# CAN-Adapter_3_2korr_0622.net
KiCad netlist of a schematic drawn in EAGLE
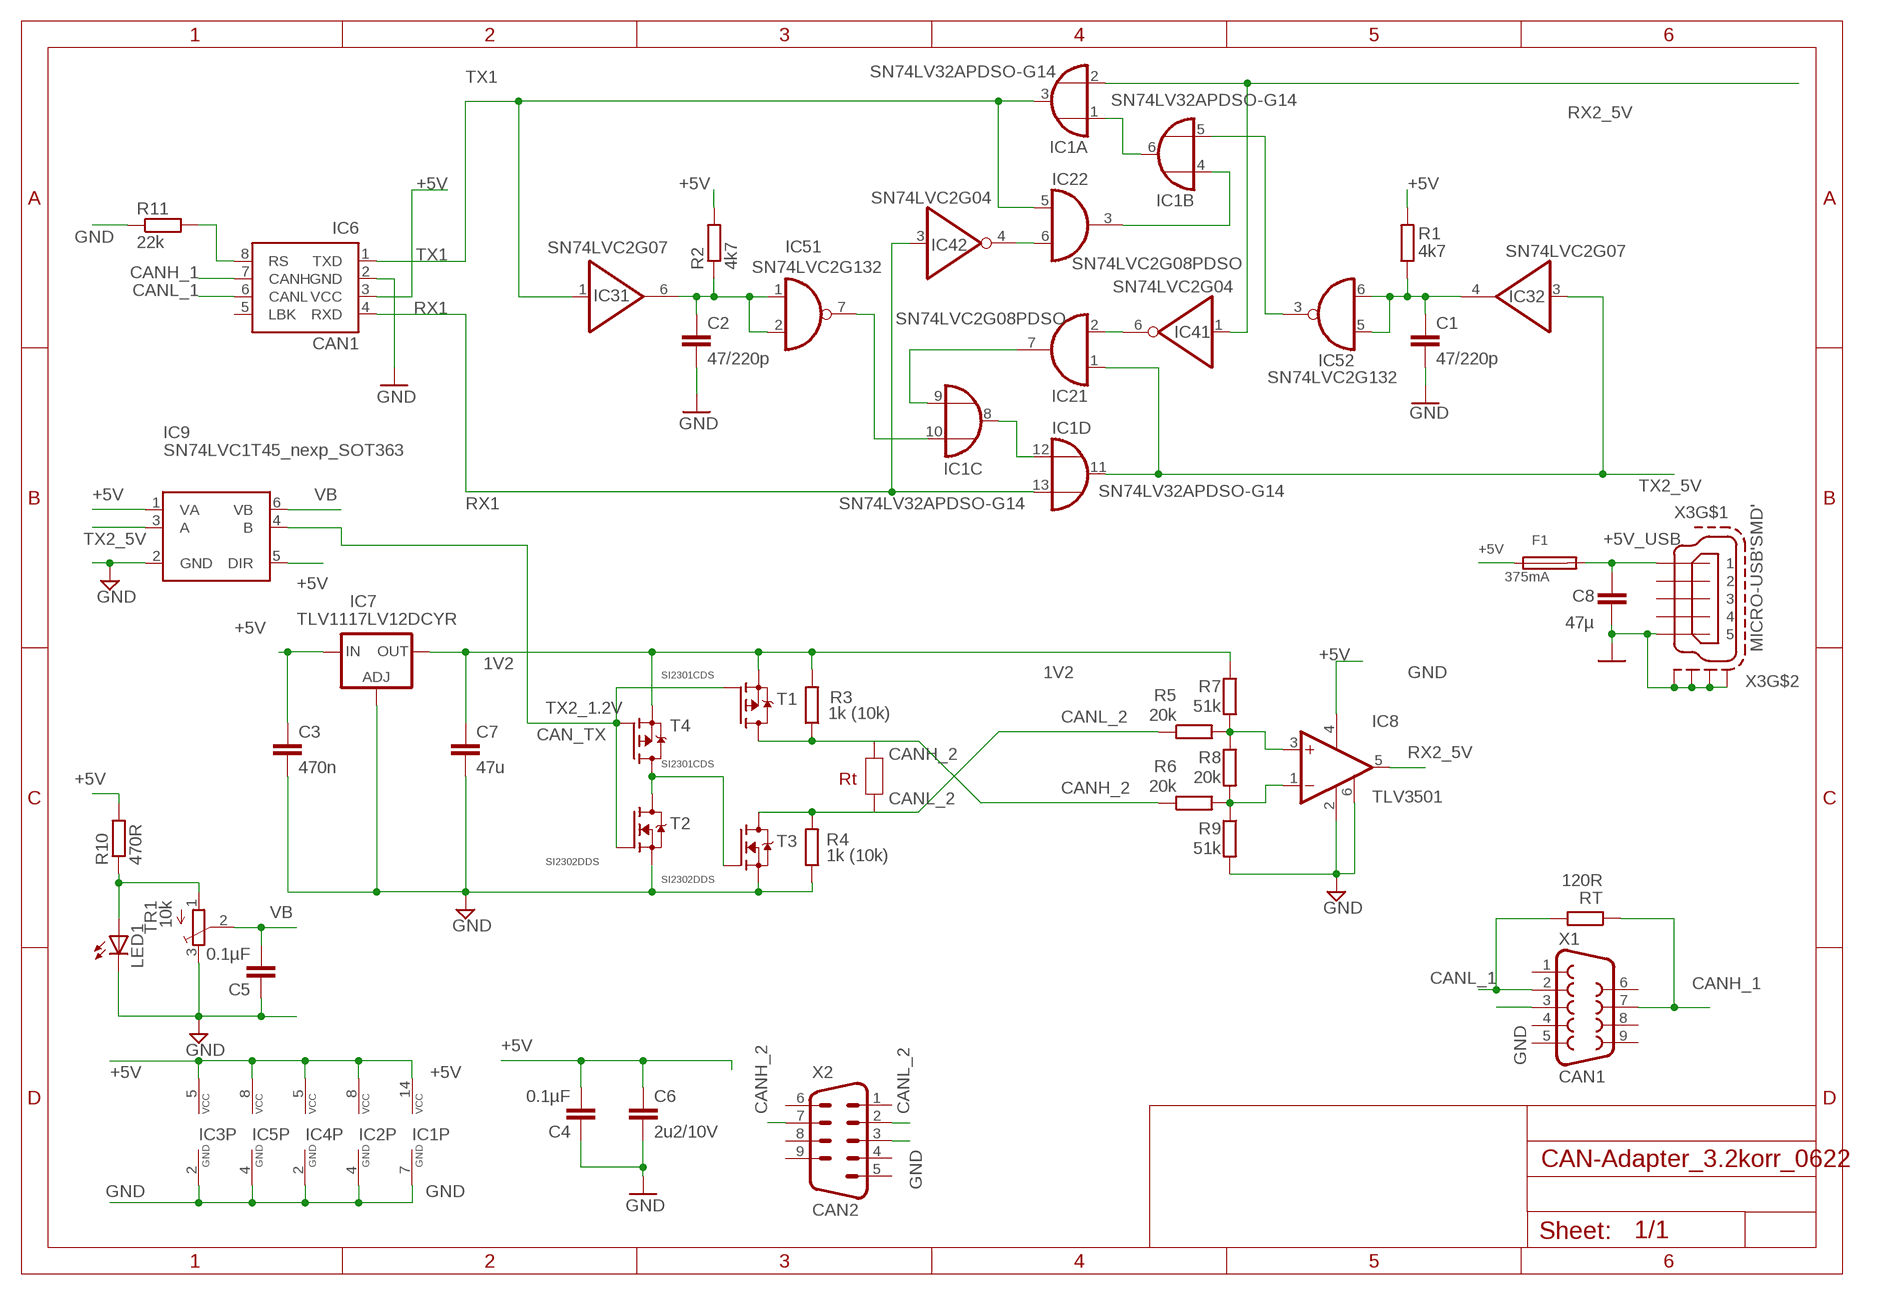
[diagram p0: schematic, sheet 1]

(export (version "E")
  (design (tool "Eeschema 10.0.6"))
  (components
    (comp (ref "C1")
      (value "47/220p")
      (footprint "eagle-import:C0603")
      (libsource (lib "eagle-import") (part "C-EUC0603"))
    )
    (comp (ref "C2")
      (value "47/220p")
      (footprint "eagle-import:C0603")
      (libsource (lib "eagle-import") (part "C-EUC0603"))
    )
    (comp (ref "C3")
      (value "470n")
      (footprint "eagle-import:C1206S")
      (libsource (lib "eagle-import") (part "C-EUC1206S"))
    )
    (comp (ref "C4")
      (value "0.1µF")
      (footprint "eagle-import:C0805")
      (libsource (lib "eagle-import") (part "C-EUC0805"))
    )
    (comp (ref "C5")
      (value "0.1µF")
      (footprint "eagle-import:C0805")
      (libsource (lib "eagle-import") (part "C-EUC0805"))
    )
    (comp (ref "C6")
      (value "2u2/10V")
      (footprint "eagle-import:C0805")
      (libsource (lib "eagle-import") (part "C-EUC0805"))
    )
    (comp (ref "C7")
      (value "47u")
      (footprint "eagle-import:C1206K")
      (libsource (lib "eagle-import") (part "C-EUC1206K"))
    )
    (comp (ref "C8")
      (value "47µ")
      (footprint "eagle-import:C1206K")
      (libsource (lib "eagle-import") (part "C-EUC1206K"))
    )
    (comp (ref "F1")
      (value "375mA")
      (footprint "eagle-import:1206")
      (libsource (lib "eagle-import") (part "SMD-FUSE1206"))
    )
    (comp (ref "IC1")
      (value "SN74LV32APDSO-G14")
      (footprint "eagle-import:PW_R-PDSO-G14")
      (libsource (lib "eagle-import") (part "SN74LV32APDSO-G14"))
    )
    (comp (ref "IC2")
      (value "SN74LVC2G08PDSO")
      (footprint "eagle-import:R-PDSO-G08_DCT")
      (libsource (lib "eagle-import") (part "SN74LVC2G08PDSO"))
    )
    (comp (ref "IC3")
      (value "SN74LVC2G07")
      (footprint "eagle-import:R-PDSO-G06")
      (libsource (lib "eagle-import") (part "SN74LVC2G07DCK"))
    )
    (comp (ref "IC4")
      (value "SN74LVC2G04")
      (footprint "eagle-import:R-PDSO-G06")
      (libsource (lib "eagle-import") (part "SN74LVC2G04DCK"))
    )
    (comp (ref "IC5")
      (value "SN74LVC2G132")
      (footprint "eagle-import:S-PDSO-G08_DCU")
      (libsource (lib "eagle-import") (part "SN74LVC2G132DCU"))
    )
    (comp (ref "IC6")
      (value "CAN1")
      (footprint "eagle-import:SO-08")
      (libsource (lib "eagle-import") (part "SN65233SO-08''"))
    )
    (comp (ref "IC7")
      (value "TLV1117LV12DCYR")
      (footprint "eagle-import:SOT223")
      (libsource (lib "eagle-import") (part "LD117A?S12TR"))
    )
    (comp (ref "IC8")
      (value "TLV3501")
      (footprint "eagle-import:SOT23-6")
      (libsource (lib "eagle-import") (part "TLV3501"))
    )
    (comp (ref "IC9")
      (value "SN74LVC1T45_nexp_SOT363")
      (footprint "eagle-import:SOT363")
      (libsource (lib "eagle-import") (part "SN74AVCH1T45SOT363"))
    )
    (comp (ref "LED1")
      (value "LED3MM")
      (footprint "eagle-import:LED3MM")
      (libsource (lib "eagle-import") (part "LED3MM"))
    )
    (comp (ref "R1")
      (value "4k7")
      (footprint "eagle-import:R0603")
      (libsource (lib "eagle-import") (part "R-EU_R0603"))
    )
    (comp (ref "R2")
      (value "4k7")
      (footprint "eagle-import:R0603")
      (libsource (lib "eagle-import") (part "R-EU_R0603"))
    )
    (comp (ref "R3")
      (value "1k (10k)")
      (footprint "eagle-import:R0603")
      (libsource (lib "eagle-import") (part "R-EU_R0603"))
    )
    (comp (ref "R4")
      (value "1k (10k)")
      (footprint "eagle-import:R0603")
      (libsource (lib "eagle-import") (part "R-EU_R0603"))
    )
    (comp (ref "R5")
      (value "20k")
      (footprint "eagle-import:R0603")
      (libsource (lib "eagle-import") (part "R-EU_R0603"))
    )
    (comp (ref "R6")
      (value "20k")
      (footprint "eagle-import:R0603")
      (libsource (lib "eagle-import") (part "R-EU_R0603"))
    )
    (comp (ref "R7")
      (value "51k")
      (footprint "eagle-import:R0603")
      (libsource (lib "eagle-import") (part "R-EU_R0603"))
    )
    (comp (ref "R8")
      (value "20k")
      (footprint "eagle-import:R0603")
      (libsource (lib "eagle-import") (part "R-EU_R0603"))
    )
    (comp (ref "R9")
      (value "51k")
      (footprint "eagle-import:R0603")
      (libsource (lib "eagle-import") (part "R-EU_R0603"))
    )
    (comp (ref "R10")
      (value "470R")
      (footprint "eagle-import:R0603")
      (libsource (lib "eagle-import") (part "R-EU_R0603"))
    )
    (comp (ref "R11")
      (value "22k")
      (footprint "eagle-import:R0603")
      (libsource (lib "eagle-import") (part "R-EU_R0603"))
    )
    (comp (ref "RT")
      (value "120R")
      (footprint "eagle-import:R0603")
      (libsource (lib "eagle-import") (part "R-EU_R0603"))
    )
    (comp (ref "T1")
      (value "SI2301CDS")
      (footprint "eagle-import:SOT23")
      (libsource (lib "eagle-import") (part "SI2301CDS_PMOS"))
    )
    (comp (ref "T2")
      (value "SI2302DDS")
      (footprint "eagle-import:SOT23")
      (libsource (lib "eagle-import") (part "SI2302DDS_NMOS"))
    )
    (comp (ref "T3")
      (value "SI2302DDS")
      (footprint "eagle-import:SOT23")
      (libsource (lib "eagle-import") (part "SI2302DDS_NMOS"))
    )
    (comp (ref "T4")
      (value "SI2301CDS")
      (footprint "eagle-import:SOT23")
      (libsource (lib "eagle-import") (part "SI2301CDS_PMOS"))
    )
    (comp (ref "TR1")
      (value "10k")
      (footprint "eagle-import:TC33X-2")
      (libsource (lib "eagle-import") (part "TRIM_EU-TC33X-2"))
    )
    (comp (ref "X1")
      (value "CAN1")
      (footprint "eagle-import:F09D")
      (libsource (lib "eagle-import") (part "F09D"))
    )
    (comp (ref "X2")
      (value "CAN2")
      (footprint "eagle-import:M09D")
      (libsource (lib "eagle-import") (part "M09D"))
    )
    (comp (ref "X3")
      (value "MICRO-USB'SMD'")
      (footprint "eagle-import:MICRO-USB_SMD")
      (libsource (lib "eagle-import") (part "MICRO-USB'SMD'"))
    )
  )
  (nets
    (net (code "1") (name "/+5V") (class "Default")
      (node (ref "C3") (pin "1") (pinfunction "1_1") (pintype "passive"))
      (node (ref "C4") (pin "2") (pinfunction "2_2") (pintype "passive"))
      (node (ref "C6") (pin "1") (pinfunction "1_1") (pintype "passive"))
      (node (ref "F1") (pin "P$1") (pinfunction "1_P$1") (pintype "passive"))
      (node (ref "IC1") (pin "14") (pinfunction "VCC_14") (pintype "power_in"))
      (node (ref "IC2") (pin "8") (pinfunction "VCC_8") (pintype "power_in"))
      (node (ref "IC3") (pin "5") (pinfunction "VCC_5") (pintype "power_in"))
      (node (ref "IC4") (pin "5") (pinfunction "VCC_5") (pintype "power_in"))
      (node (ref "IC5") (pin "8") (pinfunction "VCC_8") (pintype "power_in"))
      (node (ref "IC6") (pin "3") (pinfunction "VCC_3") (pintype "input"))
      (node (ref "IC7") (pin "3") (pinfunction "IN_3") (pintype "input"))
      (node (ref "IC8") (pin "4") (pinfunction "V+_4") (pintype "power_in"))
      (node (ref "IC9") (pin "1") (pinfunction "VA_1") (pintype "power_in"))
      (node (ref "IC9") (pin "5") (pinfunction "DIR_5") (pintype "bidirectional"))
      (node (ref "R1") (pin "2") (pinfunction "2_2") (pintype "passive"))
      (node (ref "R10") (pin "2") (pinfunction "2_2") (pintype "passive"))
      (node (ref "R2") (pin "2") (pinfunction "2_2") (pintype "passive"))
    )
    (net (code "2") (name "/+5V_USB") (class "Default")
      (node (ref "C8") (pin "1") (pinfunction "1_1") (pintype "passive"))
      (node (ref "F1") (pin "P$2") (pinfunction "2_P$2") (pintype "passive"))
      (node (ref "X3") (pin "P$1") (pinfunction "1_P$1") (pintype "passive"))
    )
    (net (code "3") (name "/1V2") (class "Default")
      (node (ref "C7") (pin "1") (pinfunction "1_1") (pintype "passive"))
      (node (ref "IC7") (pin "4") (pinfunction "OUT_4") (pintype "passive"))
      (node (ref "R3") (pin "2") (pinfunction "2_2") (pintype "passive"))
      (node (ref "R7") (pin "1") (pinfunction "1_1") (pintype "passive"))
      (node (ref "T1") (pin "2") (pinfunction "S_2") (pintype "passive"))
      (node (ref "T4") (pin "2") (pinfunction "S_2") (pintype "passive"))
    )
    (net (code "4") (name "/CANH_1") (class "Default")
      (node (ref "IC6") (pin "7") (pinfunction "CANH_7") (pintype "input"))
      (node (ref "RT") (pin "1") (pinfunction "1_1") (pintype "passive"))
      (node (ref "X1") (pin "7") (pinfunction "7_7") (pintype "passive"))
    )
    (net (code "5") (name "/CANH_2") (class "Default")
      (node (ref "R3") (pin "1") (pinfunction "1_1") (pintype "passive"))
      (node (ref "R6") (pin "1") (pinfunction "1_1") (pintype "passive"))
      (node (ref "T1") (pin "3") (pinfunction "D_3") (pintype "passive"))
      (node (ref "X2") (pin "7") (pinfunction "7_7") (pintype "passive"))
    )
    (net (code "6") (name "/CANL_1") (class "Default")
      (node (ref "IC6") (pin "6") (pinfunction "CANL_6") (pintype "input"))
      (node (ref "RT") (pin "2") (pinfunction "2_2") (pintype "passive"))
      (node (ref "X1") (pin "2") (pinfunction "2_2") (pintype "passive"))
    )
    (net (code "7") (name "/CANL_2") (class "Default")
      (node (ref "R4") (pin "2") (pinfunction "2_2") (pintype "passive"))
      (node (ref "R5") (pin "1") (pinfunction "1_1") (pintype "passive"))
      (node (ref "T3") (pin "3") (pinfunction "D_3") (pintype "passive"))
      (node (ref "X2") (pin "2") (pinfunction "2_2") (pintype "passive"))
    )
    (net (code "8") (name "/RX1") (class "Default")
      (node (ref "IC1") (pin "13") (pinfunction "I1_13") (pintype "input"))
      (node (ref "IC4") (pin "3") (pinfunction "A_3") (pintype "input"))
      (node (ref "IC6") (pin "4") (pinfunction "RXD_4") (pintype "input"))
    )
    (net (code "9") (name "/RX2_5V") (class "Default")
      (node (ref "IC1") (pin "2") (pinfunction "I1_2") (pintype "input"))
      (node (ref "IC4") (pin "1") (pinfunction "A_1") (pintype "input"))
      (node (ref "IC8") (pin "5") (pinfunction "OUT_5") (pintype "output"))
    )
    (net (code "10") (name "/TX1") (class "Default")
      (node (ref "IC1") (pin "3") (pinfunction "O_3") (pintype "output"))
      (node (ref "IC2") (pin "5") (pinfunction "A_5") (pintype "input"))
      (node (ref "IC3") (pin "1") (pinfunction "A_1") (pintype "input"))
      (node (ref "IC6") (pin "1") (pinfunction "TXD_1") (pintype "input"))
    )
    (net (code "11") (name "/TX2_1.2V") (class "Default")
      (node (ref "IC9") (pin "4") (pinfunction "B_4") (pintype "bidirectional"))
      (node (ref "T1") (pin "1") (pinfunction "G_1") (pintype "passive"))
      (node (ref "T2") (pin "1") (pinfunction "G_1") (pintype "passive"))
      (node (ref "T4") (pin "1") (pinfunction "G_1") (pintype "passive"))
    )
    (net (code "12") (name "/TX2_5V") (class "Default")
      (node (ref "IC1") (pin "11") (pinfunction "O_11") (pintype "output"))
      (node (ref "IC2") (pin "1") (pinfunction "A_1") (pintype "input"))
      (node (ref "IC3") (pin "3") (pinfunction "A_3") (pintype "input"))
      (node (ref "IC9") (pin "3") (pinfunction "A_3") (pintype "bidirectional"))
    )
    (net (code "13") (name "/VB") (class "Default")
      (node (ref "C5") (pin "2") (pinfunction "2_2") (pintype "passive"))
      (node (ref "IC9") (pin "6") (pinfunction "VB_6") (pintype "power_in"))
      (node (ref "TR1") (pin "2") (pinfunction "S_2") (pintype "passive"))
    )
    (net (code "14") (name "GND") (class "Default")
      (node (ref "C1") (pin "2") (pinfunction "2_2") (pintype "passive"))
      (node (ref "C2") (pin "2") (pinfunction "2_2") (pintype "passive"))
      (node (ref "C3") (pin "2") (pinfunction "2_2") (pintype "passive"))
      (node (ref "C4") (pin "1") (pinfunction "1_1") (pintype "passive"))
      (node (ref "C5") (pin "1") (pinfunction "1_1") (pintype "passive"))
      (node (ref "C6") (pin "2") (pinfunction "2_2") (pintype "passive"))
      (node (ref "C7") (pin "2") (pinfunction "2_2") (pintype "passive"))
      (node (ref "C8") (pin "2") (pinfunction "2_2") (pintype "passive"))
      (node (ref "IC1") (pin "7") (pinfunction "GND_7") (pintype "power_in"))
      (node (ref "IC2") (pin "4") (pinfunction "GND_4") (pintype "power_in"))
      (node (ref "IC3") (pin "2") (pinfunction "GND_2") (pintype "power_in"))
      (node (ref "IC4") (pin "2") (pinfunction "GND_2") (pintype "power_in"))
      (node (ref "IC5") (pin "4") (pinfunction "GND_4") (pintype "power_in"))
      (node (ref "IC6") (pin "2") (pinfunction "GND_2") (pintype "input"))
      (node (ref "IC7") (pin "1") (pinfunction "ADJ_1") (pintype "input"))
      (node (ref "IC8") (pin "2") (pinfunction "V-_2") (pintype "power_in"))
      (node (ref "IC8") (pin "6") (pinfunction "SHDN_6") (pintype "bidirectional"))
      (node (ref "IC9") (pin "2") (pinfunction "GND_2") (pintype "power_in"))
      (node (ref "LED1") (pin "K") (pinfunction "C_K") (pintype "passive"))
      (node (ref "R11") (pin "1") (pinfunction "1_1") (pintype "passive"))
      (node (ref "R4") (pin "1") (pinfunction "1_1") (pintype "passive"))
      (node (ref "R9") (pin "2") (pinfunction "2_2") (pintype "passive"))
      (node (ref "T2") (pin "2") (pinfunction "S_2") (pintype "passive"))
      (node (ref "T3") (pin "2") (pinfunction "S_2") (pintype "passive"))
      (node (ref "TR1") (pin "3") (pinfunction "E_3") (pintype "passive"))
      (node (ref "X1") (pin "3") (pinfunction "3_3") (pintype "passive"))
      (node (ref "X2") (pin "3") (pinfunction "3_3") (pintype "passive"))
      (node (ref "X3") (pin "P$5") (pinfunction "5_P$5") (pintype "passive"))
      (node (ref "X3") (pin "P$6") (pinfunction "S1_P$6") (pintype "passive"))
      (node (ref "X3") (pin "P$7") (pinfunction "S2_P$7") (pintype "passive"))
      (node (ref "X3") (pin "P$8") (pinfunction "S3_P$8") (pintype "passive"))
      (node (ref "X3") (pin "P$9") (pinfunction "S4_P$9") (pintype "passive"))
    )
    (net (code "15") (name "Net-(IC1A-I0)") (class "Default")
      (node (ref "IC1") (pin "1") (pinfunction "I0_1") (pintype "input"))
      (node (ref "IC1") (pin "6") (pinfunction "O_6") (pintype "output"))
    )
    (net (code "16") (name "Net-(IC1B-I0)") (class "Default")
      (node (ref "IC1") (pin "4") (pinfunction "I0_4") (pintype "input"))
      (node (ref "IC2") (pin "3") (pinfunction "Y_3") (pintype "output"))
    )
    (net (code "17") (name "Net-(IC1B-I1)") (class "Default")
      (node (ref "IC1") (pin "5") (pinfunction "I1_5") (pintype "input"))
      (node (ref "IC5") (pin "3") (pinfunction "Y_3") (pintype "output"))
    )
    (net (code "18") (name "Net-(IC1C-I0)") (class "Default")
      (node (ref "IC1") (pin "9") (pinfunction "I0_9") (pintype "input"))
      (node (ref "IC2") (pin "7") (pinfunction "Y_7") (pintype "output"))
    )
    (net (code "19") (name "Net-(IC1C-I1)") (class "Default")
      (node (ref "IC1") (pin "10") (pinfunction "I1_10") (pintype "input"))
      (node (ref "IC5") (pin "7") (pinfunction "Y_7") (pintype "output"))
    )
    (net (code "20") (name "Net-(IC1C-O)") (class "Default")
      (node (ref "IC1") (pin "12") (pinfunction "I0_12") (pintype "input"))
      (node (ref "IC1") (pin "8") (pinfunction "O_8") (pintype "output"))
    )
    (net (code "21") (name "Net-(IC2A-B)") (class "Default")
      (node (ref "IC2") (pin "2") (pinfunction "B_2") (pintype "input"))
      (node (ref "IC4") (pin "6") (pinfunction "Y_6") (pintype "output"))
    )
    (net (code "22") (name "Net-(IC2B-B)") (class "Default")
      (node (ref "IC2") (pin "6") (pinfunction "B_6") (pintype "input"))
      (node (ref "IC4") (pin "4") (pinfunction "Y_4") (pintype "output"))
    )
    (net (code "23") (name "Net-(IC3A-Y)") (class "Default")
      (node (ref "C2") (pin "1") (pinfunction "1_1") (pintype "passive"))
      (node (ref "IC3") (pin "6") (pinfunction "Y_6") (pintype "open_collector"))
      (node (ref "IC5") (pin "1") (pinfunction "A_1") (pintype "input"))
      (node (ref "IC5") (pin "2") (pinfunction "B_2") (pintype "input"))
      (node (ref "R2") (pin "1") (pinfunction "1_1") (pintype "passive"))
    )
    (net (code "24") (name "Net-(IC3B-Y)") (class "Default")
      (node (ref "C1") (pin "1") (pinfunction "1_1") (pintype "passive"))
      (node (ref "IC3") (pin "4") (pinfunction "Y_4") (pintype "open_collector"))
      (node (ref "IC5") (pin "5") (pinfunction "A_5") (pintype "input"))
      (node (ref "IC5") (pin "6") (pinfunction "B_6") (pintype "input"))
      (node (ref "R1") (pin "1") (pinfunction "1_1") (pintype "passive"))
    )
    (net (code "25") (name "Net-(IC6-RS)") (class "Default")
      (node (ref "IC6") (pin "8") (pinfunction "RS_8") (pintype "input"))
      (node (ref "R11") (pin "2") (pinfunction "2_2") (pintype "passive"))
    )
    (net (code "26") (name "Net-(IC8-+IN)") (class "Default")
      (node (ref "IC8") (pin "3") (pinfunction "+IN_3") (pintype "input"))
      (node (ref "R5") (pin "2") (pinfunction "2_2") (pintype "passive"))
      (node (ref "R7") (pin "2") (pinfunction "2_2") (pintype "passive"))
      (node (ref "R8") (pin "1") (pinfunction "1_1") (pintype "passive"))
    )
    (net (code "27") (name "Net-(IC8--IN)") (class "Default")
      (node (ref "IC8") (pin "1") (pinfunction "-IN_1") (pintype "input"))
      (node (ref "R6") (pin "2") (pinfunction "2_2") (pintype "passive"))
      (node (ref "R8") (pin "2") (pinfunction "2_2") (pintype "passive"))
      (node (ref "R9") (pin "1") (pinfunction "1_1") (pintype "passive"))
    )
    (net (code "28") (name "Net-(T2-D)") (class "Default")
      (node (ref "T2") (pin "3") (pinfunction "D_3") (pintype "passive"))
      (node (ref "T3") (pin "1") (pinfunction "G_1") (pintype "passive"))
      (node (ref "T4") (pin "3") (pinfunction "D_3") (pintype "passive"))
    )
    (net (code "29") (name "Net-(TR1-A)") (class "Default")
      (node (ref "LED1") (pin "A") (pinfunction "A_A") (pintype "passive"))
      (node (ref "R10") (pin "1") (pinfunction "1_1") (pintype "passive"))
      (node (ref "TR1") (pin "1") (pinfunction "A_1") (pintype "passive"))
    )
    (net (code "30") (name "unconnected-(IC6-LBK-Pad5)") (class "Default")
      (node (ref "IC6") (pin "5") (pinfunction "LBK_5") (pintype "input"))
    )
    (net (code "31") (name "unconnected-(X1-Pad1)") (class "Default")
      (node (ref "X1") (pin "1") (pinfunction "1_1") (pintype "passive"))
    )
    (net (code "32") (name "unconnected-(X1-Pad4)") (class "Default")
      (node (ref "X1") (pin "4") (pinfunction "4_4") (pintype "passive"))
    )
    (net (code "33") (name "unconnected-(X1-Pad5)") (class "Default")
      (node (ref "X1") (pin "5") (pinfunction "5_5") (pintype "passive"))
    )
    (net (code "34") (name "unconnected-(X1-Pad6)") (class "Default")
      (node (ref "X1") (pin "6") (pinfunction "6_6") (pintype "passive"))
    )
    (net (code "35") (name "unconnected-(X1-Pad8)") (class "Default")
      (node (ref "X1") (pin "8") (pinfunction "8_8") (pintype "passive"))
    )
    (net (code "36") (name "unconnected-(X1-Pad9)") (class "Default")
      (node (ref "X1") (pin "9") (pinfunction "9_9") (pintype "passive"))
    )
    (net (code "37") (name "unconnected-(X2-Pad1)") (class "Default")
      (node (ref "X2") (pin "1") (pinfunction "1_1") (pintype "passive"))
    )
    (net (code "38") (name "unconnected-(X2-Pad4)") (class "Default")
      (node (ref "X2") (pin "4") (pinfunction "4_4") (pintype "passive"))
    )
    (net (code "39") (name "unconnected-(X2-Pad5)") (class "Default")
      (node (ref "X2") (pin "5") (pinfunction "5_5") (pintype "passive"))
    )
    (net (code "40") (name "unconnected-(X2-Pad6)") (class "Default")
      (node (ref "X2") (pin "6") (pinfunction "6_6") (pintype "passive"))
    )
    (net (code "41") (name "unconnected-(X2-Pad8)") (class "Default")
      (node (ref "X2") (pin "8") (pinfunction "8_8") (pintype "passive"))
    )
    (net (code "42") (name "unconnected-(X2-Pad9)") (class "Default")
      (node (ref "X2") (pin "9") (pinfunction "9_9") (pintype "passive"))
    )
    (net (code "43") (name "unconnected-(X3A-2-PadP$2)") (class "Default")
      (node (ref "X3") (pin "P$2") (pinfunction "2_P$2") (pintype "passive"))
    )
    (net (code "44") (name "unconnected-(X3A-3-PadP$3)") (class "Default")
      (node (ref "X3") (pin "P$3") (pinfunction "3_P$3") (pintype "passive"))
    )
    (net (code "45") (name "unconnected-(X3A-4-PadP$4)") (class "Default")
      (node (ref "X3") (pin "P$4") (pinfunction "4_P$4") (pintype "passive"))
    )
  )
)
